# A-star_dual_dc_motor2a.net
KiCad netlist of a schematic drawn in EAGLE
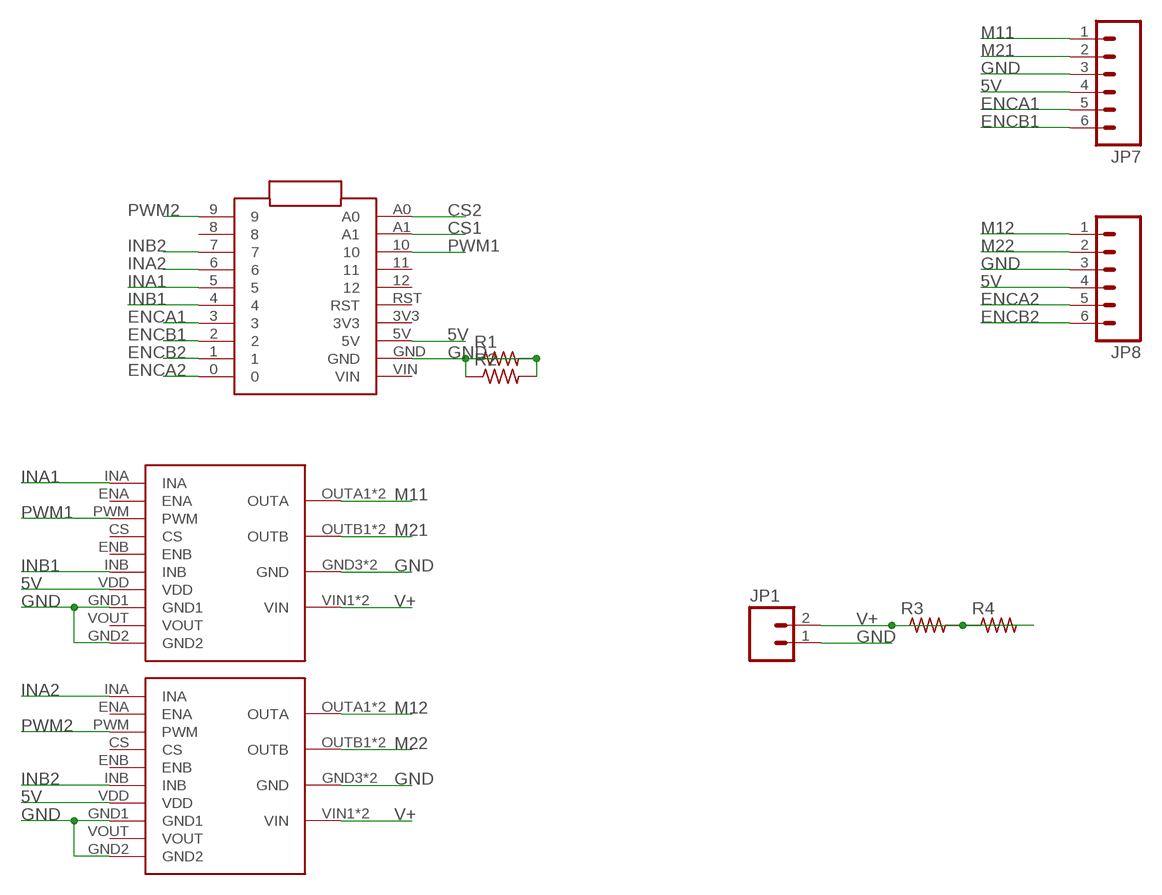
[diagram p0: schematic, sheet 1]

(export (version "E")
  (design (tool "Eeschema 10.0.6"))
  (components
    (comp (ref "ALL_PADS1")
      (value "POLOLU_VNH5019_CARRIER")
      (footprint "eagle-import:VNH5019_CARRIER")
      (libsource (lib "eagle-import") (part "POLOLU_VNH5019_CARRIER"))
    )
    (comp (ref "ALL_PADS2")
      (value "POLOLU_VNH5019_CARRIER")
      (footprint "eagle-import:VNH5019_CARRIER")
      (libsource (lib "eagle-import") (part "POLOLU_VNH5019_CARRIER"))
    )
    (comp (ref "JP1")
      (value "M023.5MM")
      (footprint "eagle-import:SCREWTERMINAL-3.5MM-2")
      (libsource (lib "eagle-import") (part "M023.5MM"))
    )
    (comp (ref "JP7")
      (value "M06SIP")
      (footprint "eagle-import:1X06")
      (libsource (lib "eagle-import") (part "M06SIP"))
    )
    (comp (ref "JP8")
      (value "M06SIP")
      (footprint "eagle-import:1X06")
      (libsource (lib "eagle-import") (part "M06SIP"))
    )
    (comp (ref "R1")
      (value "RES-US1206FAB")
      (footprint "eagle-import:R1206FAB")
      (libsource (lib "eagle-import") (part "RES-US1206FAB"))
    )
    (comp (ref "R2")
      (value "RES-US1206FAB")
      (footprint "eagle-import:R1206FAB")
      (libsource (lib "eagle-import") (part "RES-US1206FAB"))
    )
    (comp (ref "R3")
      (value "RES-US1206FAB")
      (footprint "eagle-import:R1206FAB")
      (libsource (lib "eagle-import") (part "RES-US1206FAB"))
    )
    (comp (ref "R4")
      (value "RES-US1206FAB")
      (footprint "eagle-import:R1206FAB")
      (libsource (lib "eagle-import") (part "RES-US1206FAB"))
    )
    (comp (ref "U$1")
      (value "POLOLU_A-STAR-MICRO")
      (footprint "eagle-import:POLOLU_A-STAR-MICRO")
      (libsource (lib "eagle-import") (part "POLOLU_A-STAR-MICRO"))
    )
  )
  (nets
    (net (code "1") (name "/5V") (class "Default")
      (node (ref "ALL_PADS1") (pin "VDD") (pinfunction "VDD_VDD") (pintype "bidirectional"))
      (node (ref "ALL_PADS2") (pin "VDD") (pinfunction "VDD_VDD") (pintype "bidirectional"))
      (node (ref "JP7") (pin "4") (pinfunction "4_4") (pintype "passive"))
      (node (ref "JP8") (pin "4") (pinfunction "4_4") (pintype "passive"))
      (node (ref "U$1") (pin "5V") (pinfunction "5V_5V") (pintype "bidirectional"))
    )
    (net (code "2") (name "/CS1") (class "Default")
      (node (ref "U$1") (pin "A1") (pinfunction "A1_A1") (pintype "bidirectional"))
    )
    (net (code "3") (name "/CS2") (class "Default")
      (node (ref "U$1") (pin "A0") (pinfunction "A0_A0") (pintype "bidirectional"))
    )
    (net (code "4") (name "/ENCA1") (class "Default")
      (node (ref "JP7") (pin "5") (pinfunction "5_5") (pintype "passive"))
      (node (ref "U$1") (pin "3") (pinfunction "3_3") (pintype "bidirectional"))
    )
    (net (code "5") (name "/ENCA2") (class "Default")
      (node (ref "JP8") (pin "5") (pinfunction "5_5") (pintype "passive"))
      (node (ref "U$1") (pin "0") (pinfunction "0_0") (pintype "bidirectional"))
    )
    (net (code "6") (name "/ENCB1") (class "Default")
      (node (ref "JP7") (pin "6") (pinfunction "6_6") (pintype "passive"))
      (node (ref "U$1") (pin "2") (pinfunction "2_2") (pintype "bidirectional"))
    )
    (net (code "7") (name "/ENCB2") (class "Default")
      (node (ref "JP8") (pin "6") (pinfunction "6_6") (pintype "passive"))
      (node (ref "U$1") (pin "1") (pinfunction "1_1") (pintype "bidirectional"))
    )
    (net (code "8") (name "/GND") (class "Default")
      (node (ref "ALL_PADS1") (pin "GND1") (pinfunction "GND1_GND1") (pintype "bidirectional"))
      (node (ref "ALL_PADS1") (pin "GND2") (pinfunction "GND2_GND2") (pintype "bidirectional"))
      (node (ref "ALL_PADS1") (pin "GND3") (pinfunction "GND_GND3") (pintype "bidirectional"))
      (node (ref "ALL_PADS1") (pin "GND4") (pinfunction "GND_GND4") (pintype "bidirectional"))
      (node (ref "ALL_PADS2") (pin "GND1") (pinfunction "GND1_GND1") (pintype "bidirectional"))
      (node (ref "ALL_PADS2") (pin "GND2") (pinfunction "GND2_GND2") (pintype "bidirectional"))
      (node (ref "ALL_PADS2") (pin "GND3") (pinfunction "GND_GND3") (pintype "bidirectional"))
      (node (ref "ALL_PADS2") (pin "GND4") (pinfunction "GND_GND4") (pintype "bidirectional"))
      (node (ref "JP1") (pin "1") (pinfunction "1_1") (pintype "passive"))
      (node (ref "JP7") (pin "3") (pinfunction "3_3") (pintype "passive"))
      (node (ref "JP8") (pin "3") (pinfunction "3_3") (pintype "passive"))
      (node (ref "R1") (pin "1") (pinfunction "1_1") (pintype "passive"))
      (node (ref "R1") (pin "2") (pinfunction "2_2") (pintype "passive"))
      (node (ref "R2") (pin "1") (pinfunction "1_1") (pintype "passive"))
      (node (ref "R2") (pin "2") (pinfunction "2_2") (pintype "passive"))
      (node (ref "U$1") (pin "GND") (pinfunction "GND_GND") (pintype "bidirectional"))
    )
    (net (code "9") (name "/INA1") (class "Default")
      (node (ref "ALL_PADS1") (pin "INA") (pinfunction "INA_INA") (pintype "bidirectional"))
      (node (ref "U$1") (pin "5") (pinfunction "5_5") (pintype "bidirectional"))
    )
    (net (code "10") (name "/INA2") (class "Default")
      (node (ref "ALL_PADS2") (pin "INA") (pinfunction "INA_INA") (pintype "bidirectional"))
      (node (ref "U$1") (pin "6") (pinfunction "6_6") (pintype "bidirectional"))
    )
    (net (code "11") (name "/INB1") (class "Default")
      (node (ref "ALL_PADS1") (pin "INB") (pinfunction "INB_INB") (pintype "bidirectional"))
      (node (ref "U$1") (pin "4") (pinfunction "4_4") (pintype "bidirectional"))
    )
    (net (code "12") (name "/INB2") (class "Default")
      (node (ref "ALL_PADS2") (pin "INB") (pinfunction "INB_INB") (pintype "bidirectional"))
      (node (ref "U$1") (pin "7") (pinfunction "7_7") (pintype "bidirectional"))
    )
    (net (code "13") (name "/M11") (class "Default")
      (node (ref "ALL_PADS1") (pin "OUTA1") (pinfunction "OUTA_OUTA1") (pintype "bidirectional"))
      (node (ref "ALL_PADS1") (pin "OUTA2") (pinfunction "OUTA_OUTA2") (pintype "bidirectional"))
      (node (ref "JP7") (pin "1") (pinfunction "1_1") (pintype "passive"))
    )
    (net (code "14") (name "/M12") (class "Default")
      (node (ref "ALL_PADS2") (pin "OUTA1") (pinfunction "OUTA_OUTA1") (pintype "bidirectional"))
      (node (ref "ALL_PADS2") (pin "OUTA2") (pinfunction "OUTA_OUTA2") (pintype "bidirectional"))
      (node (ref "JP8") (pin "1") (pinfunction "1_1") (pintype "passive"))
    )
    (net (code "15") (name "/M21") (class "Default")
      (node (ref "ALL_PADS1") (pin "OUTB1") (pinfunction "OUTB_OUTB1") (pintype "bidirectional"))
      (node (ref "ALL_PADS1") (pin "OUTB2") (pinfunction "OUTB_OUTB2") (pintype "bidirectional"))
      (node (ref "JP7") (pin "2") (pinfunction "2_2") (pintype "passive"))
    )
    (net (code "16") (name "/M22") (class "Default")
      (node (ref "ALL_PADS2") (pin "OUTB1") (pinfunction "OUTB_OUTB1") (pintype "bidirectional"))
      (node (ref "ALL_PADS2") (pin "OUTB2") (pinfunction "OUTB_OUTB2") (pintype "bidirectional"))
      (node (ref "JP8") (pin "2") (pinfunction "2_2") (pintype "passive"))
    )
    (net (code "17") (name "/PWM1") (class "Default")
      (node (ref "ALL_PADS1") (pin "PWM") (pinfunction "PWM_PWM") (pintype "bidirectional"))
      (node (ref "U$1") (pin "10") (pinfunction "10_10") (pintype "bidirectional"))
    )
    (net (code "18") (name "/PWM2") (class "Default")
      (node (ref "ALL_PADS2") (pin "PWM") (pinfunction "PWM_PWM") (pintype "bidirectional"))
      (node (ref "U$1") (pin "9") (pinfunction "9_9") (pintype "bidirectional"))
    )
    (net (code "19") (name "/V+") (class "Default")
      (node (ref "ALL_PADS1") (pin "VIN1") (pinfunction "VIN_VIN1") (pintype "bidirectional"))
      (node (ref "ALL_PADS1") (pin "VIN2") (pinfunction "VIN_VIN2") (pintype "bidirectional"))
      (node (ref "ALL_PADS2") (pin "VIN1") (pinfunction "VIN_VIN1") (pintype "bidirectional"))
      (node (ref "ALL_PADS2") (pin "VIN2") (pinfunction "VIN_VIN2") (pintype "bidirectional"))
      (node (ref "JP1") (pin "2") (pinfunction "2_2") (pintype "passive"))
      (node (ref "R3") (pin "1") (pinfunction "1_1") (pintype "passive"))
      (node (ref "R3") (pin "2") (pinfunction "2_2") (pintype "passive"))
      (node (ref "R4") (pin "1") (pinfunction "1_1") (pintype "passive"))
      (node (ref "R4") (pin "2") (pinfunction "2_2") (pintype "passive"))
    )
    (net (code "20") (name "unconnected-(ALL_PADS1-PadCS)") (class "Default")
      (node (ref "ALL_PADS1") (pin "CS") (pinfunction "CS_CS") (pintype "bidirectional"))
    )
    (net (code "21") (name "unconnected-(ALL_PADS1-PadENA)") (class "Default")
      (node (ref "ALL_PADS1") (pin "ENA") (pinfunction "ENA_ENA") (pintype "bidirectional"))
    )
    (net (code "22") (name "unconnected-(ALL_PADS1-PadENB)") (class "Default")
      (node (ref "ALL_PADS1") (pin "ENB") (pinfunction "ENB_ENB") (pintype "bidirectional"))
    )
    (net (code "23") (name "unconnected-(ALL_PADS1-PadVOUT)") (class "Default")
      (node (ref "ALL_PADS1") (pin "VOUT") (pinfunction "VOUT_VOUT") (pintype "bidirectional"))
    )
    (net (code "24") (name "unconnected-(ALL_PADS2-PadCS)") (class "Default")
      (node (ref "ALL_PADS2") (pin "CS") (pinfunction "CS_CS") (pintype "bidirectional"))
    )
    (net (code "25") (name "unconnected-(ALL_PADS2-PadENA)") (class "Default")
      (node (ref "ALL_PADS2") (pin "ENA") (pinfunction "ENA_ENA") (pintype "bidirectional"))
    )
    (net (code "26") (name "unconnected-(ALL_PADS2-PadENB)") (class "Default")
      (node (ref "ALL_PADS2") (pin "ENB") (pinfunction "ENB_ENB") (pintype "bidirectional"))
    )
    (net (code "27") (name "unconnected-(ALL_PADS2-PadVOUT)") (class "Default")
      (node (ref "ALL_PADS2") (pin "VOUT") (pinfunction "VOUT_VOUT") (pintype "bidirectional"))
    )
    (net (code "28") (name "unconnected-(U$1-Pad3V3)") (class "Default")
      (node (ref "U$1") (pin "3V3") (pinfunction "3V3_3V3") (pintype "bidirectional"))
    )
    (net (code "29") (name "unconnected-(U$1-Pad8)") (class "Default")
      (node (ref "U$1") (pin "8") (pinfunction "8_8") (pintype "bidirectional"))
    )
    (net (code "30") (name "unconnected-(U$1-Pad11)") (class "Default")
      (node (ref "U$1") (pin "11") (pinfunction "11_11") (pintype "bidirectional"))
    )
    (net (code "31") (name "unconnected-(U$1-Pad12)") (class "Default")
      (node (ref "U$1") (pin "12") (pinfunction "12_12") (pintype "bidirectional"))
    )
    (net (code "32") (name "unconnected-(U$1-PadRST)") (class "Default")
      (node (ref "U$1") (pin "RST") (pinfunction "RST_RST") (pintype "bidirectional"))
    )
    (net (code "33") (name "unconnected-(U$1-PadVIN)") (class "Default")
      (node (ref "U$1") (pin "VIN") (pinfunction "VIN_VIN") (pintype "bidirectional"))
    )
  )
)
